# MoteinoM0_mic_v0_4.net
KiCad netlist of a schematic drawn in EAGLE
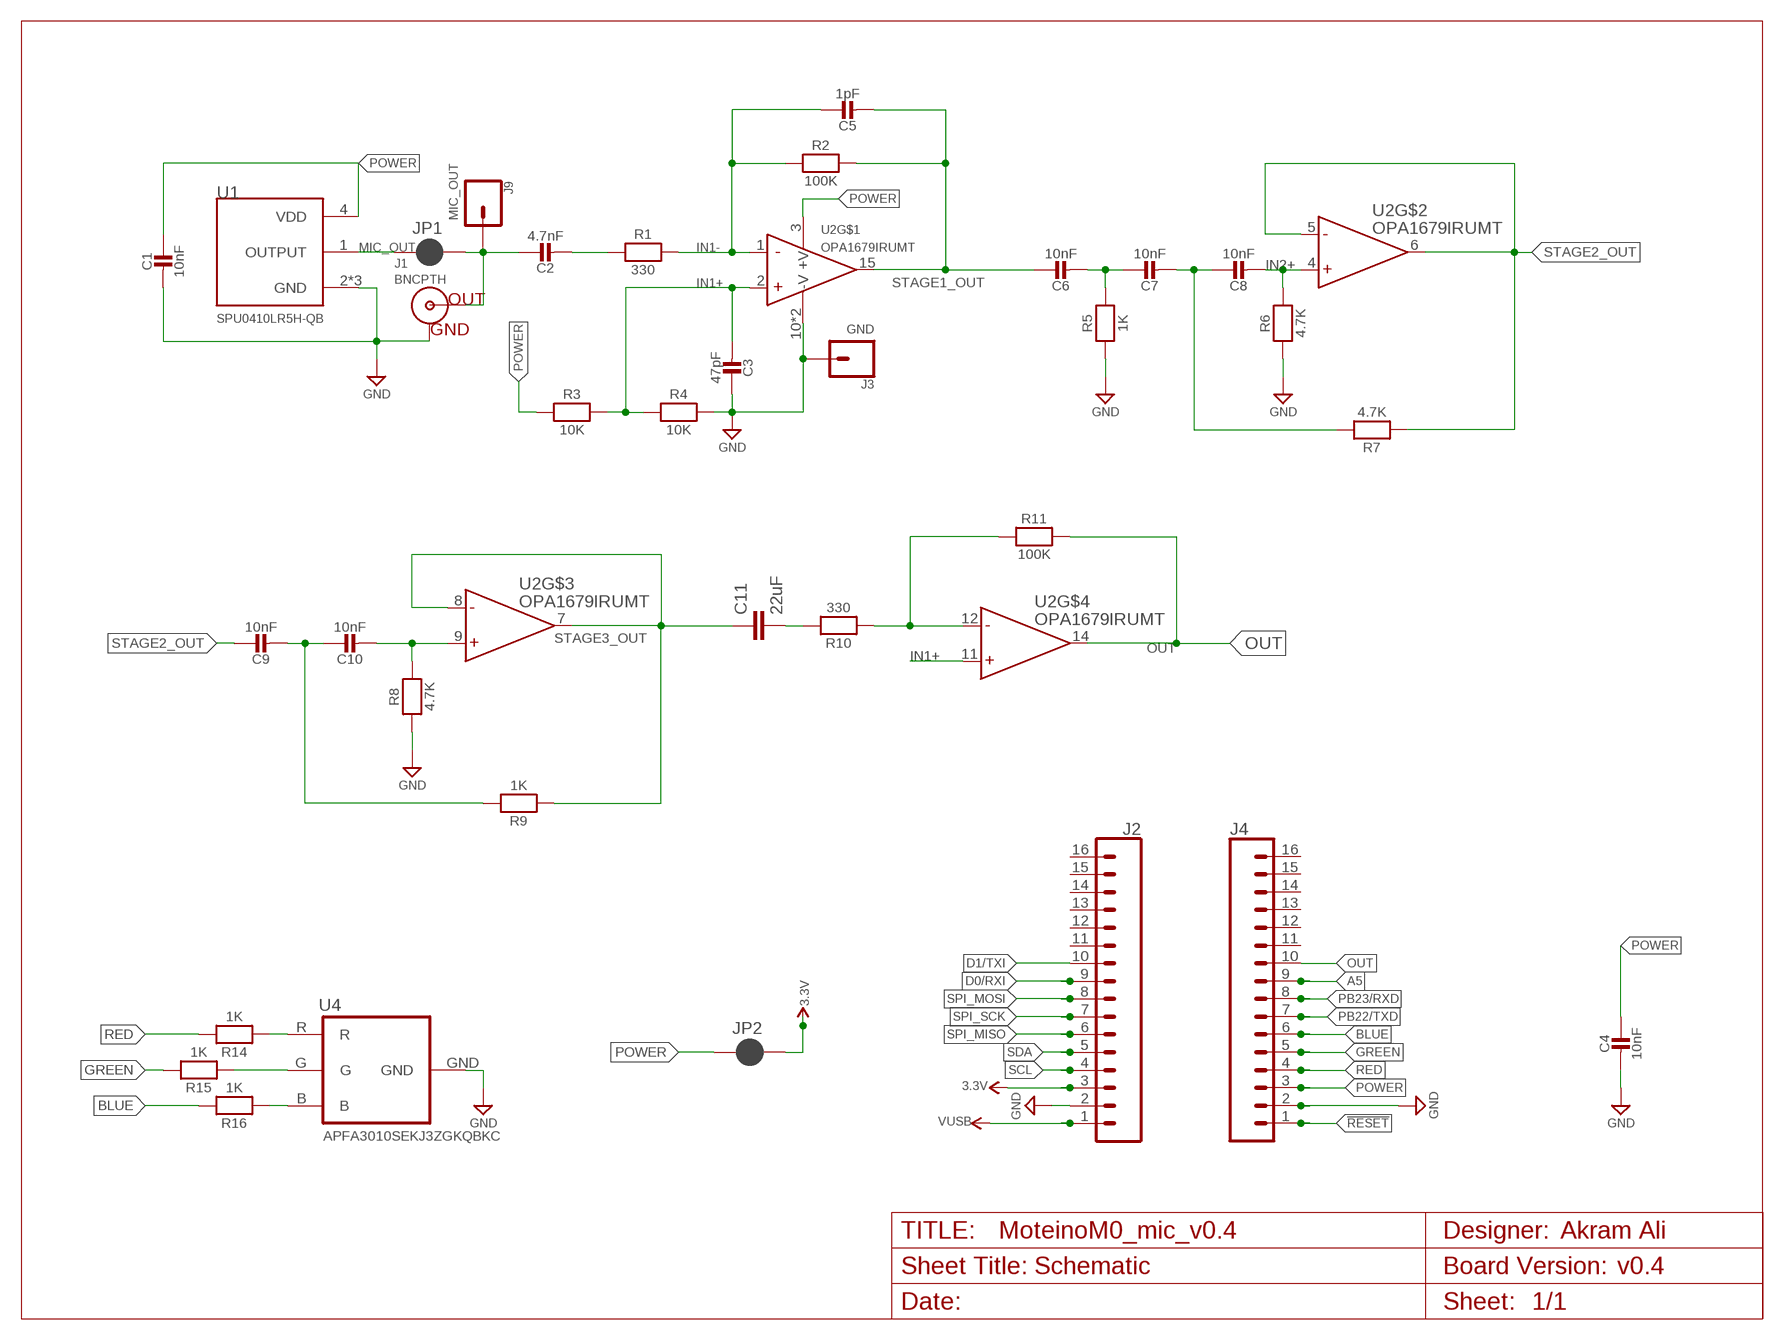
[diagram p0: schematic, sheet 1]

(export (version "E")
  (design (tool "Eeschema 10.0.6"))
  (components
    (comp (ref "C1")
      (value "10nF")
      (footprint "eagle-import:MICROBUILDER__0402MP")
      (fields (field (name "MPN") "GRM155R71H104KE14J"))
      (libsource (lib "eagle-import") (part "MICROBUILDER_CAP_CERAMIC_0402MP"))
    )
    (comp (ref "C2")
      (value "4.7nF")
      (footprint "eagle-import:MICROBUILDER__0402MP")
      (fields (field (name "MPN") "GRM155R71H104KE14J"))
      (libsource (lib "eagle-import") (part "MICROBUILDER_CAP_CERAMIC_0402MP"))
    )
    (comp (ref "C3")
      (value "47pF")
      (footprint "eagle-import:MICROBUILDER__0402MP")
      (fields (field (name "MPN") "GRM155R71H104KE14J"))
      (libsource (lib "eagle-import") (part "MICROBUILDER_CAP_CERAMIC_0402MP"))
    )
    (comp (ref "C4")
      (value "10nF")
      (footprint "eagle-import:MICROBUILDER__0402MP")
      (fields (field (name "MPN") "GRM155R71H104KE14J"))
      (libsource (lib "eagle-import") (part "MICROBUILDER_CAP_CERAMIC_0402MP"))
    )
    (comp (ref "C5")
      (value "1pF")
      (footprint "eagle-import:MICROBUILDER__0402MP")
      (fields (field (name "MPN") "GRM155R71H104KE14J"))
      (libsource (lib "eagle-import") (part "MICROBUILDER_CAP_CERAMIC_0402MP"))
    )
    (comp (ref "C6")
      (value "10nF")
      (footprint "eagle-import:MICROBUILDER__0402MP")
      (fields (field (name "MPN") "GRM155R71H104KE14J"))
      (libsource (lib "eagle-import") (part "MICROBUILDER_CAP_CERAMIC_0402MP"))
    )
    (comp (ref "C7")
      (value "10nF")
      (footprint "eagle-import:MICROBUILDER__0402MP")
      (fields (field (name "MPN") "GRM155R71H104KE14J"))
      (libsource (lib "eagle-import") (part "MICROBUILDER_CAP_CERAMIC_0402MP"))
    )
    (comp (ref "C8")
      (value "10nF")
      (footprint "eagle-import:MICROBUILDER__0402MP")
      (fields (field (name "MPN") "GRM155R71H104KE14J"))
      (libsource (lib "eagle-import") (part "MICROBUILDER_CAP_CERAMIC_0402MP"))
    )
    (comp (ref "C9")
      (value "10nF")
      (footprint "eagle-import:MICROBUILDER__0402MP")
      (fields (field (name "MPN") "GRM155R71H104KE14J"))
      (libsource (lib "eagle-import") (part "MICROBUILDER_CAP_CERAMIC_0402MP"))
    )
    (comp (ref "C10")
      (value "10nF")
      (footprint "eagle-import:MICROBUILDER__0402MP")
      (fields (field (name "MPN") "GRM155R71H104KE14J"))
      (libsource (lib "eagle-import") (part "MICROBUILDER_CAP_CERAMIC_0402MP"))
    )
    (comp (ref "C11")
      (value "22uF")
      (footprint "eagle-import:0805")
      (libsource (lib "eagle-import") (part "CAP0805"))
    )
    (comp (ref "J1")
      (value "BNCPTH")
      (footprint "eagle-import:BNC")
      (libsource (lib "eagle-import") (part "BNCPTH"))
    )
    (comp (ref "J2")
      (value "CONN_161X16_NO_SILK")
      (footprint "eagle-import:1X16_NO_SILK")
      (libsource (lib "eagle-import") (part "CONN_161X16_NO_SILK"))
    )
    (comp (ref "J3")
      (value "GND")
      (footprint "eagle-import:1X01")
      (libsource (lib "eagle-import") (part "CONN_01"))
    )
    (comp (ref "J4")
      (value "CONN_161X16_NO_SILK")
      (footprint "eagle-import:1X16_NO_SILK")
      (libsource (lib "eagle-import") (part "CONN_161X16_NO_SILK"))
    )
    (comp (ref "J9")
      (value "MIC_OUT")
      (footprint "eagle-import:1X01")
      (libsource (lib "eagle-import") (part "CONN_01"))
    )
    (comp (ref "JP1")
      (value "JUMPER-SMT_2_NC_PASTE_SILK")
      (footprint "eagle-import:SMT-JUMPER_2_NC_PASTE_SILK")
      (libsource (lib "eagle-import") (part "JUMPER-SMT_2_NC_PASTE_SILK"))
    )
    (comp (ref "JP2")
      (value "JUMPER-SMT_2_NC_PASTE_SILK")
      (footprint "eagle-import:SMT-JUMPER_2_NC_PASTE_SILK")
      (libsource (lib "eagle-import") (part "JUMPER-SMT_2_NC_PASTE_SILK"))
    )
    (comp (ref "R1")
      (value "330")
      (footprint "eagle-import:MICROBUILDER__0402MP")
      (fields (field (name "MPN") "RC0402FR-074K7P"))
      (libsource (lib "eagle-import") (part "MICROBUILDER_RESISTOR_0402MP"))
    )
    (comp (ref "R2")
      (value "100K")
      (footprint "eagle-import:MICROBUILDER__0402MP")
      (fields (field (name "MPN") "RC0402FR-074K7P"))
      (libsource (lib "eagle-import") (part "MICROBUILDER_RESISTOR_0402MP"))
    )
    (comp (ref "R3")
      (value "10K")
      (footprint "eagle-import:MICROBUILDER__0402MP")
      (fields (field (name "MPN") "RC0402FR-074K7P"))
      (libsource (lib "eagle-import") (part "MICROBUILDER_RESISTOR_0402MP"))
    )
    (comp (ref "R4")
      (value "10K")
      (footprint "eagle-import:MICROBUILDER__0402MP")
      (fields (field (name "MPN") "RC0402FR-074K7P"))
      (libsource (lib "eagle-import") (part "MICROBUILDER_RESISTOR_0402MP"))
    )
    (comp (ref "R5")
      (value "1K")
      (footprint "eagle-import:MICROBUILDER__0402MP")
      (fields (field (name "MPN") "RC0402FR-074K7P"))
      (libsource (lib "eagle-import") (part "MICROBUILDER_RESISTOR_0402MP"))
    )
    (comp (ref "R6")
      (value "4.7K")
      (footprint "eagle-import:MICROBUILDER__0402MP")
      (fields (field (name "MPN") "RC0402FR-074K7P"))
      (libsource (lib "eagle-import") (part "MICROBUILDER_RESISTOR_0402MP"))
    )
    (comp (ref "R7")
      (value "4.7K")
      (footprint "eagle-import:MICROBUILDER__0402MP")
      (fields (field (name "MPN") "RC0402FR-074K7P"))
      (libsource (lib "eagle-import") (part "MICROBUILDER_RESISTOR_0402MP"))
    )
    (comp (ref "R8")
      (value "4.7K")
      (footprint "eagle-import:MICROBUILDER__0402MP")
      (fields (field (name "MPN") "RC0402FR-074K7P"))
      (libsource (lib "eagle-import") (part "MICROBUILDER_RESISTOR_0402MP"))
    )
    (comp (ref "R9")
      (value "1K")
      (footprint "eagle-import:MICROBUILDER__0402MP")
      (fields (field (name "MPN") "RC0402FR-074K7P"))
      (libsource (lib "eagle-import") (part "MICROBUILDER_RESISTOR_0402MP"))
    )
    (comp (ref "R10")
      (value "330")
      (footprint "eagle-import:MICROBUILDER__0402MP")
      (fields (field (name "MPN") "RC0402FR-074K7P"))
      (libsource (lib "eagle-import") (part "MICROBUILDER_RESISTOR_0402MP"))
    )
    (comp (ref "R11")
      (value "100K")
      (footprint "eagle-import:MICROBUILDER__0402MP")
      (fields (field (name "MPN") "RC0402FR-074K7P"))
      (libsource (lib "eagle-import") (part "MICROBUILDER_RESISTOR_0402MP"))
    )
    (comp (ref "R14")
      (value "1K")
      (footprint "eagle-import:MICROBUILDER__0402MP")
      (fields (field (name "MPN") "RC0402FR-074K7P"))
      (libsource (lib "eagle-import") (part "MICROBUILDER_RESISTOR_0402MP"))
    )
    (comp (ref "R15")
      (value "1K")
      (footprint "eagle-import:MICROBUILDER__0402MP")
      (fields (field (name "MPN") "RC0402FR-074K7P"))
      (libsource (lib "eagle-import") (part "MICROBUILDER_RESISTOR_0402MP"))
    )
    (comp (ref "R16")
      (value "1K")
      (footprint "eagle-import:MICROBUILDER__0402MP")
      (fields (field (name "MPN") "RC0402FR-074K7P"))
      (libsource (lib "eagle-import") (part "MICROBUILDER_RESISTOR_0402MP"))
    )
    (comp (ref "U1")
      (value "SPU0410LR5H-QB")
      (footprint "eagle-import:XDCR_SPU0410LR5H-QB")
      (fields (field (name "MF") "Knowles"))
      (libsource (lib "eagle-import") (part "SPU0410LR5H-QB"))
    )
    (comp (ref "U2")
      (value "OPA1679IRUMT")
      (footprint "eagle-import:QFN65P400X400X80-17N")
      (libsource (lib "eagle-import") (part "OPA1679IRUMT"))
    )
    (comp (ref "U4")
      (value "APFA3010SEKJ3ZGKQBKC")
      (footprint "eagle-import:SMD-RA-4")
      (libsource (lib "eagle-import") (part "APFA3010SEKJ3ZGKQBKC"))
    )
  )
  (nets
    (net (code "1") (name "/IN1+") (class "Default")
      (node (ref "C3") (pin "2") (pinfunction "2_2") (pintype "passive"))
      (node (ref "R3") (pin "2") (pinfunction "2_2") (pintype "passive"))
      (node (ref "R4") (pin "1") (pinfunction "1_1") (pintype "passive"))
      (node (ref "U2") (pin "11") (pinfunction "+IN_11") (pintype "input"))
      (node (ref "U2") (pin "2") (pinfunction "+IN_2") (pintype "input"))
    )
    (net (code "2") (name "/IN1-") (class "Default")
      (node (ref "C5") (pin "1") (pinfunction "1_1") (pintype "passive"))
      (node (ref "R1") (pin "2") (pinfunction "2_2") (pintype "passive"))
      (node (ref "R2") (pin "1") (pinfunction "1_1") (pintype "passive"))
      (node (ref "U2") (pin "1") (pinfunction "-IN_1") (pintype "input"))
    )
    (net (code "3") (name "/IN2+") (class "Default")
      (node (ref "C8") (pin "2") (pinfunction "2_2") (pintype "passive"))
      (node (ref "R6") (pin "2") (pinfunction "2_2") (pintype "passive"))
      (node (ref "U2") (pin "4") (pinfunction "+IN_4") (pintype "input"))
    )
    (net (code "4") (name "/MIC_OUT") (class "Default")
      (node (ref "C2") (pin "1") (pinfunction "1_1") (pintype "passive"))
      (node (ref "J1") (pin "S") (pinfunction "OUT_S") (pintype "bidirectional"))
      (node (ref "J9") (pin "1") (pinfunction "1_1") (pintype "passive"))
      (node (ref "JP1") (pin "2") (pinfunction "2_2") (pintype "passive"))
    )
    (net (code "5") (name "/STAGE1_OUT") (class "Default")
      (node (ref "C5") (pin "2") (pinfunction "2_2") (pintype "passive"))
      (node (ref "C6") (pin "1") (pinfunction "1_1") (pintype "passive"))
      (node (ref "R2") (pin "2") (pinfunction "2_2") (pintype "passive"))
      (node (ref "U2") (pin "15") (pinfunction "OUT_15") (pintype "output"))
    )
    (net (code "6") (name "/STAGE3_OUT") (class "Default")
      (node (ref "C11") (pin "1") (pinfunction "1_1") (pintype "passive"))
      (node (ref "R9") (pin "1") (pinfunction "1_1") (pintype "passive"))
      (node (ref "U2") (pin "7") (pinfunction "OUT_7") (pintype "output"))
      (node (ref "U2") (pin "8") (pinfunction "-IN_8") (pintype "input"))
    )
    (net (code "7") (name "/~{RESET}") (class "Default")
      (node (ref "J4") (pin "1") (pinfunction "1_1") (pintype "passive"))
    )
    (net (code "8") (name "3.3V") (class "Default")
      (node (ref "J2") (pin "3") (pinfunction "3_3") (pintype "passive"))
      (node (ref "JP2") (pin "2") (pinfunction "2_2") (pintype "passive"))
    )
    (net (code "9") (name "A5") (class "Default")
      (node (ref "J4") (pin "9") (pinfunction "9_9") (pintype "passive"))
    )
    (net (code "10") (name "BLUE") (class "Default")
      (node (ref "J4") (pin "6") (pinfunction "6_6") (pintype "passive"))
      (node (ref "R16") (pin "2") (pinfunction "2_2") (pintype "passive"))
    )
    (net (code "11") (name "D0{slash}RXI") (class "Default")
      (node (ref "J2") (pin "9") (pinfunction "9_9") (pintype "passive"))
    )
    (net (code "12") (name "D1{slash}TXI") (class "Default")
      (node (ref "J2") (pin "10") (pinfunction "10_10") (pintype "passive"))
    )
    (net (code "13") (name "GND") (class "Default")
      (node (ref "C1") (pin "2") (pinfunction "2_2") (pintype "passive"))
      (node (ref "C3") (pin "1") (pinfunction "1_1") (pintype "passive"))
      (node (ref "C4") (pin "2") (pinfunction "2_2") (pintype "passive"))
      (node (ref "J1") (pin "GND") (pinfunction "GND_GND") (pintype "bidirectional"))
      (node (ref "J2") (pin "2") (pinfunction "2_2") (pintype "passive"))
      (node (ref "J3") (pin "1") (pinfunction "1_1") (pintype "passive"))
      (node (ref "J4") (pin "2") (pinfunction "2_2") (pintype "passive"))
      (node (ref "R4") (pin "2") (pinfunction "2_2") (pintype "passive"))
      (node (ref "R5") (pin "1") (pinfunction "1_1") (pintype "passive"))
      (node (ref "R6") (pin "1") (pinfunction "1_1") (pintype "passive"))
      (node (ref "R8") (pin "1") (pinfunction "1_1") (pintype "passive"))
      (node (ref "U1") (pin "2") (pinfunction "GND_2") (pintype "power_in"))
      (node (ref "U1") (pin "3") (pinfunction "GND_3") (pintype "power_in"))
      (node (ref "U1") (pin "5") (pinfunction "GND_5") (pintype "power_in"))
      (node (ref "U2") (pin "10") (pinfunction "-V_10") (pintype "power_in"))
      (node (ref "U2") (pin "17") (pinfunction "-V_17") (pintype "power_in"))
      (node (ref "U4") (pin "GND") (pinfunction "GND_GND") (pintype "bidirectional"))
    )
    (net (code "14") (name "GREEN") (class "Default")
      (node (ref "J4") (pin "5") (pinfunction "5_5") (pintype "passive"))
      (node (ref "R15") (pin "2") (pinfunction "2_2") (pintype "passive"))
    )
    (net (code "15") (name "Net-(C2-Pad2)") (class "Default")
      (node (ref "C2") (pin "2") (pinfunction "2_2") (pintype "passive"))
      (node (ref "R1") (pin "1") (pinfunction "1_1") (pintype "passive"))
    )
    (net (code "16") (name "Net-(C6-Pad2)") (class "Default")
      (node (ref "C6") (pin "2") (pinfunction "2_2") (pintype "passive"))
      (node (ref "C7") (pin "1") (pinfunction "1_1") (pintype "passive"))
      (node (ref "R5") (pin "2") (pinfunction "2_2") (pintype "passive"))
    )
    (net (code "17") (name "Net-(C7-Pad2)") (class "Default")
      (node (ref "C7") (pin "2") (pinfunction "2_2") (pintype "passive"))
      (node (ref "C8") (pin "1") (pinfunction "1_1") (pintype "passive"))
      (node (ref "R7") (pin "2") (pinfunction "2_2") (pintype "passive"))
    )
    (net (code "18") (name "Net-(C10-Pad1)") (class "Default")
      (node (ref "C10") (pin "1") (pinfunction "1_1") (pintype "passive"))
      (node (ref "C9") (pin "2") (pinfunction "2_2") (pintype "passive"))
      (node (ref "R9") (pin "2") (pinfunction "2_2") (pintype "passive"))
    )
    (net (code "19") (name "Net-(C11-Pad2)") (class "Default")
      (node (ref "C11") (pin "2") (pinfunction "2_2") (pintype "passive"))
      (node (ref "R10") (pin "2") (pinfunction "2_2") (pintype "passive"))
    )
    (net (code "20") (name "Net-(R14-Pad1)") (class "Default")
      (node (ref "R14") (pin "1") (pinfunction "1_1") (pintype "passive"))
      (node (ref "U4") (pin "R") (pinfunction "R_R") (pintype "bidirectional"))
    )
    (net (code "21") (name "Net-(R15-Pad1)") (class "Default")
      (node (ref "R15") (pin "1") (pinfunction "1_1") (pintype "passive"))
      (node (ref "U4") (pin "G") (pinfunction "G_G") (pintype "bidirectional"))
    )
    (net (code "22") (name "Net-(R16-Pad1)") (class "Default")
      (node (ref "R16") (pin "1") (pinfunction "1_1") (pintype "passive"))
      (node (ref "U4") (pin "B") (pinfunction "B_B") (pintype "bidirectional"))
    )
    (net (code "23") (name "Net-(U1-OUTPUT)") (class "Default")
      (node (ref "JP1") (pin "1") (pinfunction "1_1") (pintype "passive"))
      (node (ref "U1") (pin "1") (pinfunction "OUTPUT_1") (pintype "output"))
    )
    (net (code "24") (name "Net-(U2C-+IN)") (class "Default")
      (node (ref "C10") (pin "2") (pinfunction "2_2") (pintype "passive"))
      (node (ref "R8") (pin "2") (pinfunction "2_2") (pintype "passive"))
      (node (ref "U2") (pin "9") (pinfunction "+IN_9") (pintype "input"))
    )
    (net (code "25") (name "Net-(U2D--IN)") (class "Default")
      (node (ref "R10") (pin "1") (pinfunction "1_1") (pintype "passive"))
      (node (ref "R11") (pin "1") (pinfunction "1_1") (pintype "passive"))
      (node (ref "U2") (pin "12") (pinfunction "-IN_12") (pintype "input"))
    )
    (net (code "26") (name "OUT") (class "Default")
      (node (ref "J4") (pin "10") (pinfunction "10_10") (pintype "passive"))
      (node (ref "R11") (pin "2") (pinfunction "2_2") (pintype "passive"))
      (node (ref "U2") (pin "14") (pinfunction "OUT_14") (pintype "output"))
    )
    (net (code "27") (name "PB22{slash}TXD") (class "Default")
      (node (ref "J4") (pin "7") (pinfunction "7_7") (pintype "passive"))
    )
    (net (code "28") (name "PB23{slash}RXD") (class "Default")
      (node (ref "J4") (pin "8") (pinfunction "8_8") (pintype "passive"))
    )
    (net (code "29") (name "POWER") (class "Default")
      (node (ref "C1") (pin "1") (pinfunction "1_1") (pintype "passive"))
      (node (ref "C4") (pin "1") (pinfunction "1_1") (pintype "passive"))
      (node (ref "J4") (pin "3") (pinfunction "3_3") (pintype "passive"))
      (node (ref "JP2") (pin "1") (pinfunction "1_1") (pintype "passive"))
      (node (ref "R3") (pin "1") (pinfunction "1_1") (pintype "passive"))
      (node (ref "U1") (pin "4") (pinfunction "VDD_4") (pintype "power_in"))
      (node (ref "U2") (pin "3") (pinfunction "+V_3") (pintype "power_in"))
    )
    (net (code "30") (name "RED") (class "Default")
      (node (ref "J4") (pin "4") (pinfunction "4_4") (pintype "passive"))
      (node (ref "R14") (pin "2") (pinfunction "2_2") (pintype "passive"))
    )
    (net (code "31") (name "SCL") (class "Default")
      (node (ref "J2") (pin "4") (pinfunction "4_4") (pintype "passive"))
    )
    (net (code "32") (name "SDA") (class "Default")
      (node (ref "J2") (pin "5") (pinfunction "5_5") (pintype "passive"))
    )
    (net (code "33") (name "SPI_MISO") (class "Default")
      (node (ref "J2") (pin "6") (pinfunction "6_6") (pintype "passive"))
    )
    (net (code "34") (name "SPI_MOSI") (class "Default")
      (node (ref "J2") (pin "8") (pinfunction "8_8") (pintype "passive"))
    )
    (net (code "35") (name "SPI_SCK") (class "Default")
      (node (ref "J2") (pin "7") (pinfunction "7_7") (pintype "passive"))
    )
    (net (code "36") (name "STAGE2_OUT") (class "Default")
      (node (ref "C9") (pin "1") (pinfunction "1_1") (pintype "passive"))
      (node (ref "R7") (pin "1") (pinfunction "1_1") (pintype "passive"))
      (node (ref "U2") (pin "5") (pinfunction "-IN_5") (pintype "input"))
      (node (ref "U2") (pin "6") (pinfunction "OUT_6") (pintype "output"))
    )
    (net (code "37") (name "VUSB") (class "Default")
      (node (ref "J2") (pin "1") (pinfunction "1_1") (pintype "passive"))
    )
    (net (code "38") (name "unconnected-(J2-Pad11)") (class "Default")
      (node (ref "J2") (pin "11") (pinfunction "11_11") (pintype "passive"))
    )
    (net (code "39") (name "unconnected-(J2-Pad12)") (class "Default")
      (node (ref "J2") (pin "12") (pinfunction "12_12") (pintype "passive"))
    )
    (net (code "40") (name "unconnected-(J2-Pad13)") (class "Default")
      (node (ref "J2") (pin "13") (pinfunction "13_13") (pintype "passive"))
    )
    (net (code "41") (name "unconnected-(J2-Pad14)") (class "Default")
      (node (ref "J2") (pin "14") (pinfunction "14_14") (pintype "passive"))
    )
    (net (code "42") (name "unconnected-(J2-Pad15)") (class "Default")
      (node (ref "J2") (pin "15") (pinfunction "15_15") (pintype "passive"))
    )
    (net (code "43") (name "unconnected-(J2-Pad16)") (class "Default")
      (node (ref "J2") (pin "16") (pinfunction "16_16") (pintype "passive"))
    )
    (net (code "44") (name "unconnected-(J4-Pad11)") (class "Default")
      (node (ref "J4") (pin "11") (pinfunction "11_11") (pintype "passive"))
    )
    (net (code "45") (name "unconnected-(J4-Pad12)") (class "Default")
      (node (ref "J4") (pin "12") (pinfunction "12_12") (pintype "passive"))
    )
    (net (code "46") (name "unconnected-(J4-Pad13)") (class "Default")
      (node (ref "J4") (pin "13") (pinfunction "13_13") (pintype "passive"))
    )
    (net (code "47") (name "unconnected-(J4-Pad14)") (class "Default")
      (node (ref "J4") (pin "14") (pinfunction "14_14") (pintype "passive"))
    )
    (net (code "48") (name "unconnected-(J4-Pad15)") (class "Default")
      (node (ref "J4") (pin "15") (pinfunction "15_15") (pintype "passive"))
    )
    (net (code "49") (name "unconnected-(J4-Pad16)") (class "Default")
      (node (ref "J4") (pin "16") (pinfunction "16_16") (pintype "passive"))
    )
  )
)
